# MB_RELAY.net
KiCad netlist of a schematic drawn in Altium Designer
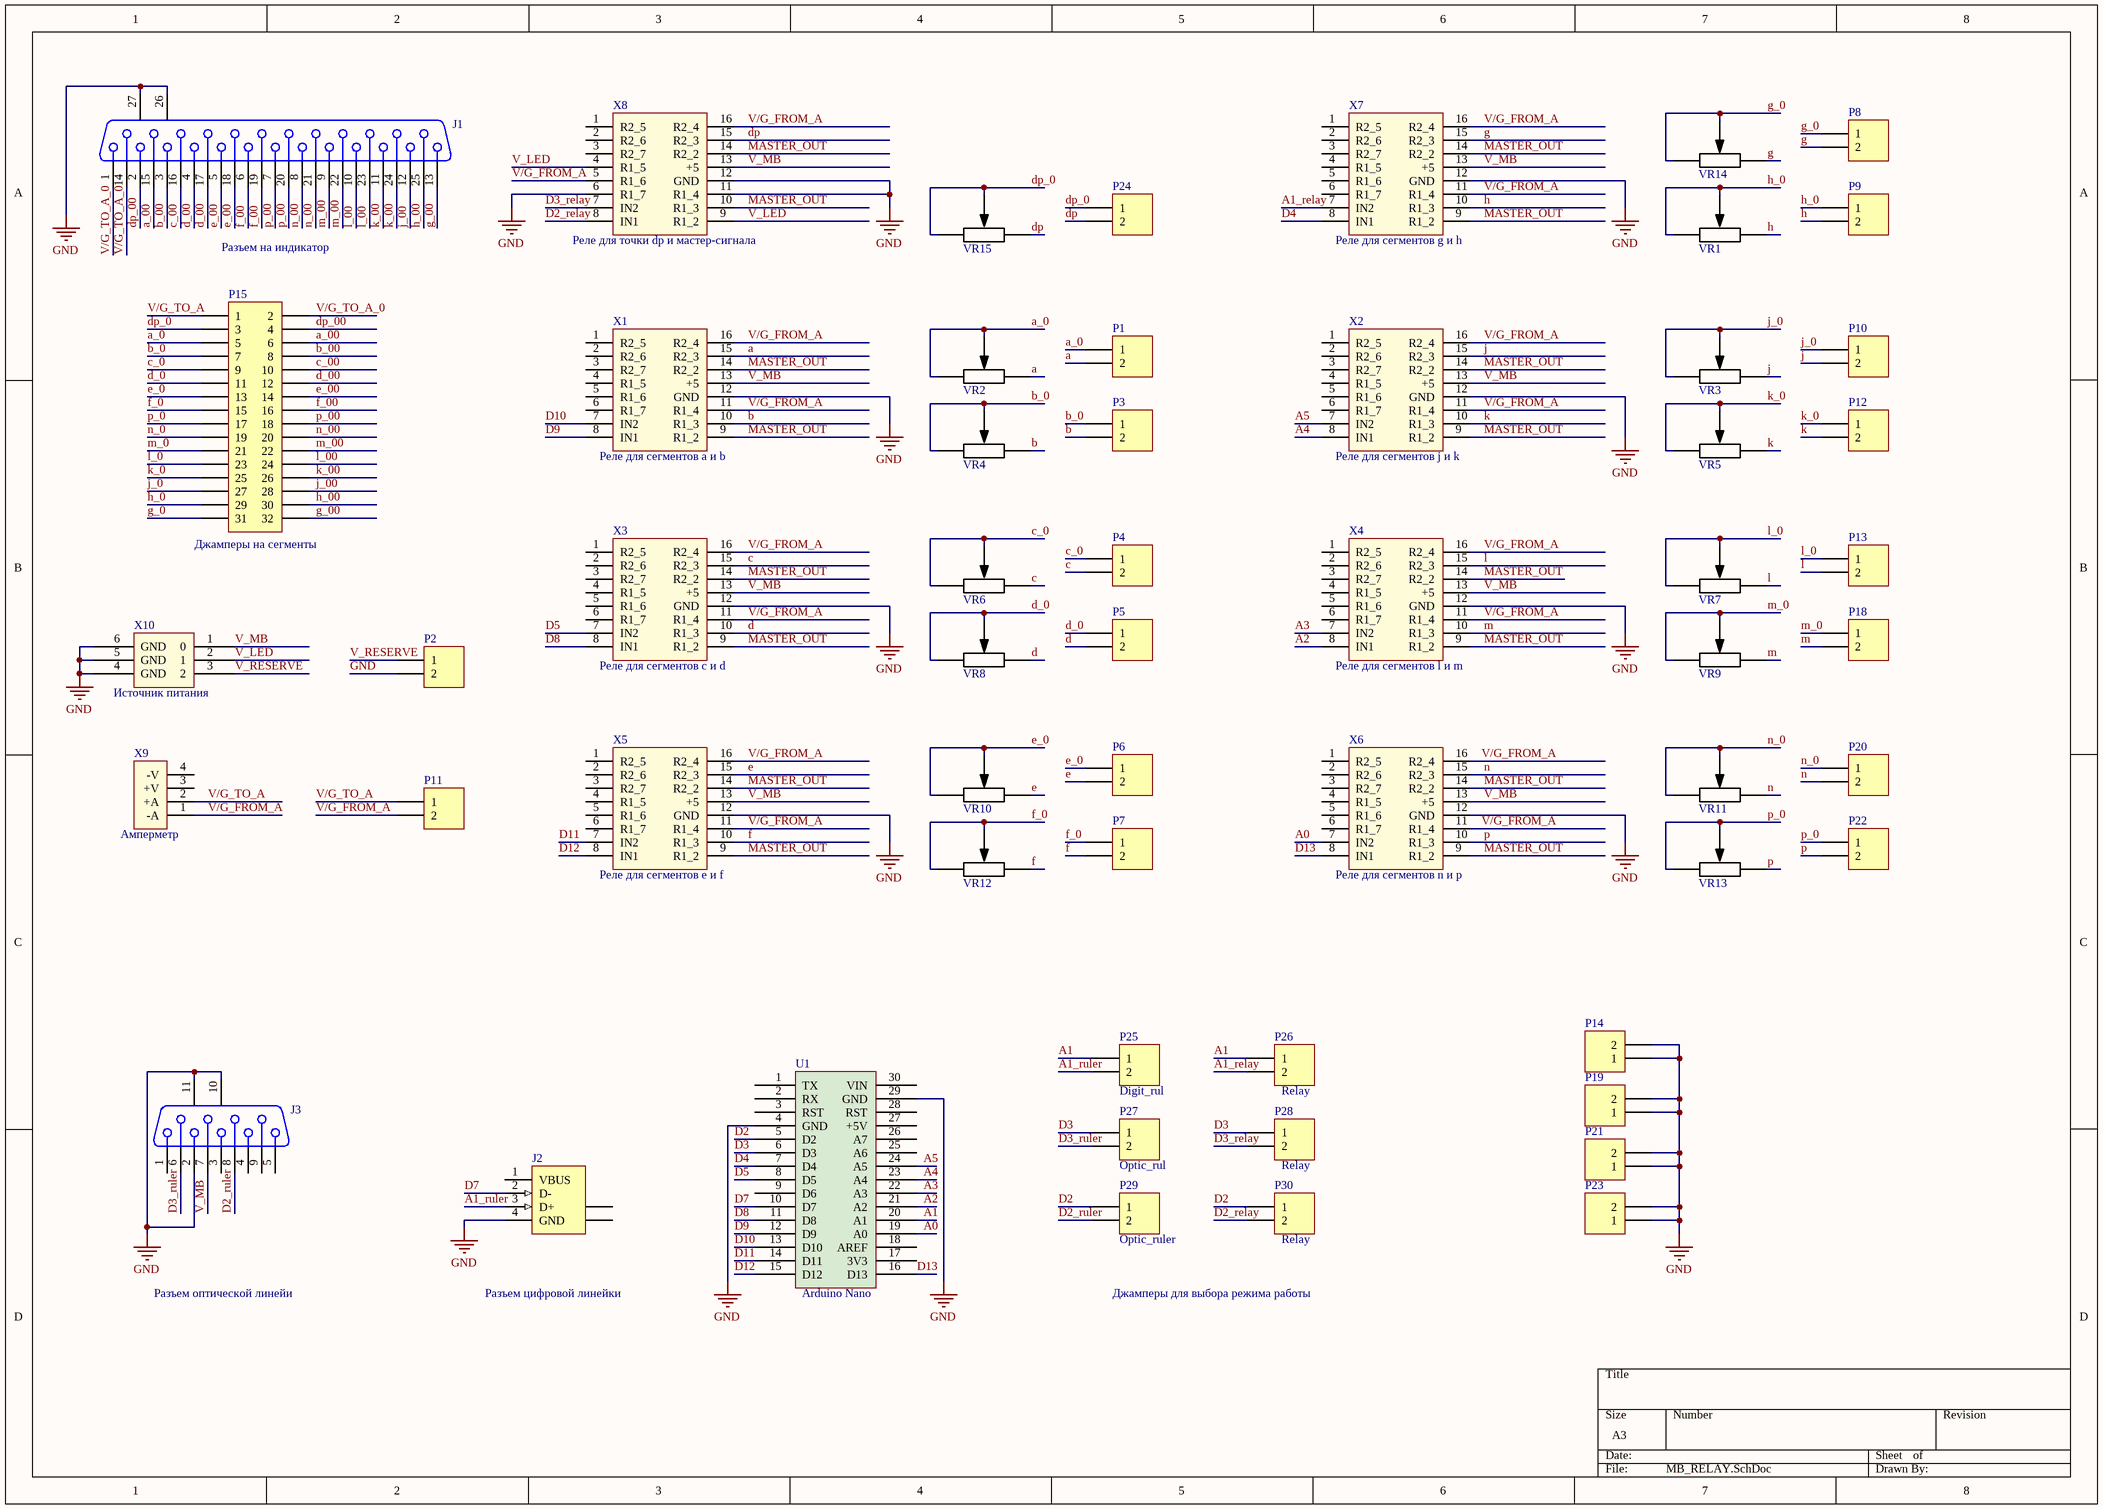
[diagram p0: MB_RELAY.SchDoc]

(export (version "E")
  (design (tool "Eeschema 10.0.6"))
  (components
    (comp (ref "J1")
      (value "D Connector 25")
      (footprint "DSUB1.385-2H25A")
      (description "Receptacle Assembly, 25 Position, Right Angle")
      (fields (field (name "PUBLISHER") "Altium Limited"))
      (libsource (lib "Miscellaneous Connectors") (part "D Connector 25"))
    )
    (comp (ref "J2")
      (value "1-353576-1")
      (footprint "353576")
      (description "USB 1.1, Right Angle, SMT, A Type, Receptacle, 4 Position, White")
      (fields (field (name "PUBLISHER") "Altium Limited"))
      (libsource (lib "AMP Serial Bus USB") (part "1-353576-1"))
    )
    (comp (ref "J3")
      (value "D Connector 9")
      (footprint "DSUB1.385-2H9")
      (description "Receptacle Assembly, 9 Position, Right Angle")
      (fields (field (name "PUBLISHER") "Altium Limited"))
      (libsource (lib "Miscellaneous Connectors") (part "D Connector 9"))
    )
    (comp (ref "P1")
      (value "Header 2")
      (footprint "HDR1X2")
      (description "Header, 2-Pin")
      (fields (field (name "PUBLISHER") "Altium Limited"))
      (libsource (lib "Miscellaneous Connectors") (part "Header 2"))
    )
    (comp (ref "P2")
      (value "Header 2")
      (footprint "HDR1X2")
      (description "Header, 2-Pin")
      (fields (field (name "PUBLISHER") "Altium Limited"))
      (libsource (lib "Miscellaneous Connectors") (part "Header 2"))
    )
    (comp (ref "P3")
      (value "Header 2")
      (footprint "HDR1X2")
      (description "Header, 2-Pin")
      (fields (field (name "PUBLISHER") "Altium Limited"))
      (libsource (lib "Miscellaneous Connectors") (part "Header 2"))
    )
    (comp (ref "P4")
      (value "Header 2")
      (footprint "HDR1X2")
      (description "Header, 2-Pin")
      (fields (field (name "PUBLISHER") "Altium Limited"))
      (libsource (lib "Miscellaneous Connectors") (part "Header 2"))
    )
    (comp (ref "P5")
      (value "Header 2")
      (footprint "HDR1X2")
      (description "Header, 2-Pin")
      (fields (field (name "PUBLISHER") "Altium Limited"))
      (libsource (lib "Miscellaneous Connectors") (part "Header 2"))
    )
    (comp (ref "P6")
      (value "GND")
      (footprint "HDR1X2")
      (description "Header, 2-Pin")
      (fields (field (name "PUBLISHER") "Altium Limited"))
      (libsource (lib "Miscellaneous Connectors") (part "Header 2"))
    )
    (comp (ref "P7")
      (value "GND")
      (footprint "HDR1X2")
      (description "Header, 2-Pin")
      (fields (field (name "PUBLISHER") "Altium Limited"))
      (libsource (lib "Miscellaneous Connectors") (part "Header 2"))
    )
    (comp (ref "P8")
      (value "GND")
      (footprint "HDR1X2")
      (description "Header, 2-Pin")
      (fields (field (name "PUBLISHER") "Altium Limited"))
      (libsource (lib "Miscellaneous Connectors") (part "Header 2"))
    )
    (comp (ref "P9")
      (value "GND")
      (footprint "HDR1X2")
      (description "Header, 2-Pin")
      (fields (field (name "PUBLISHER") "Altium Limited"))
      (libsource (lib "Miscellaneous Connectors") (part "Header 2"))
    )
    (comp (ref "P10")
      (value "Header 2")
      (footprint "HDR1X2")
      (description "Header, 2-Pin")
      (fields (field (name "PUBLISHER") "Altium Limited"))
      (libsource (lib "Miscellaneous Connectors") (part "Header 2"))
    )
    (comp (ref "P11")
      (value "Header 2")
      (footprint "HDR1X2")
      (description "Header, 2-Pin")
      (fields (field (name "PUBLISHER") "Altium Limited"))
      (libsource (lib "Miscellaneous Connectors") (part "Header 2"))
    )
    (comp (ref "P12")
      (value "Header 2")
      (footprint "HDR1X2")
      (description "Header, 2-Pin")
      (fields (field (name "PUBLISHER") "Altium Limited"))
      (libsource (lib "Miscellaneous Connectors") (part "Header 2"))
    )
    (comp (ref "P13")
      (value "GND")
      (footprint "HDR1X2")
      (description "Header, 2-Pin")
      (fields (field (name "PUBLISHER") "Altium Limited"))
      (libsource (lib "Miscellaneous Connectors") (part "Header 2"))
    )
    (comp (ref "P14")
      (value "GND")
      (footprint "HDR1X2")
      (description "Header, 2-Pin")
      (fields (field (name "PUBLISHER") "Altium Limited"))
      (libsource (lib "") (part "Header 2_1"))
    )
    (comp (ref "P15")
      (value "Header 16X2")
      (footprint "HDR2X16")
      (description "Header, 16-Pin, Dual row")
      (fields (field (name "PUBLISHER") "Altium Limited"))
      (libsource (lib "Miscellaneous Connectors") (part "Header 16X2"))
    )
    (comp (ref "P18")
      (value "GND")
      (footprint "HDR1X2")
      (description "Header, 2-Pin")
      (fields (field (name "PUBLISHER") "Altium Limited"))
      (libsource (lib "Miscellaneous Connectors") (part "Header 2"))
    )
    (comp (ref "P19")
      (value "GND")
      (footprint "HDR1X2")
      (description "Header, 2-Pin")
      (fields (field (name "PUBLISHER") "Altium Limited"))
      (libsource (lib "") (part "Header 2_1"))
    )
    (comp (ref "P20")
      (value "GND")
      (footprint "HDR1X2")
      (description "Header, 2-Pin")
      (fields (field (name "PUBLISHER") "Altium Limited"))
      (libsource (lib "Miscellaneous Connectors") (part "Header 2"))
    )
    (comp (ref "P21")
      (value "GND")
      (footprint "HDR1X2")
      (description "Header, 2-Pin")
      (fields (field (name "PUBLISHER") "Altium Limited"))
      (libsource (lib "") (part "Header 2_1"))
    )
    (comp (ref "P22")
      (value "GND")
      (footprint "HDR1X2")
      (description "Header, 2-Pin")
      (fields (field (name "PUBLISHER") "Altium Limited"))
      (libsource (lib "Miscellaneous Connectors") (part "Header 2"))
    )
    (comp (ref "P23")
      (value "GND")
      (footprint "HDR1X2")
      (description "Header, 2-Pin")
      (fields (field (name "PUBLISHER") "Altium Limited"))
      (libsource (lib "") (part "Header 2_1"))
    )
    (comp (ref "P24")
      (value "GND")
      (footprint "HDR1X2")
      (description "Header, 2-Pin")
      (fields (field (name "PUBLISHER") "Altium Limited"))
      (libsource (lib "Miscellaneous Connectors") (part "Header 2"))
    )
    (comp (ref "P25")
      (value "Digit_rul")
      (footprint "HDR1X2")
      (description "Header, 2-Pin")
      (fields (field (name "PUBLISHER") "Altium Limited"))
      (libsource (lib "Miscellaneous Connectors") (part "Header 2"))
    )
    (comp (ref "P26")
      (value "Relay")
      (footprint "HDR1X2")
      (description "Header, 2-Pin")
      (fields (field (name "PUBLISHER") "Altium Limited"))
      (libsource (lib "Miscellaneous Connectors") (part "Header 2"))
    )
    (comp (ref "P27")
      (value "Optic_rul")
      (footprint "HDR1X2")
      (description "Header, 2-Pin")
      (fields (field (name "PUBLISHER") "Altium Limited"))
      (libsource (lib "Miscellaneous Connectors") (part "Header 2"))
    )
    (comp (ref "P28")
      (value "Relay")
      (footprint "HDR1X2")
      (description "Header, 2-Pin")
      (fields (field (name "PUBLISHER") "Altium Limited"))
      (libsource (lib "Miscellaneous Connectors") (part "Header 2"))
    )
    (comp (ref "P29")
      (value "Optic_ruler")
      (footprint "HDR1X2")
      (description "Header, 2-Pin")
      (fields (field (name "PUBLISHER") "Altium Limited"))
      (libsource (lib "Miscellaneous Connectors") (part "Header 2"))
    )
    (comp (ref "P30")
      (value "Relay")
      (footprint "HDR1X2")
      (description "Header, 2-Pin")
      (fields (field (name "PUBLISHER") "Altium Limited"))
      (libsource (lib "Miscellaneous Connectors") (part "Header 2"))
    )
    (comp (ref "U1")
      (value "Arduino Nano")
      (footprint "PCBComponent_1")
      (libsource (lib "Nano") (part "Component_1"))
    )
    (comp (ref "VR1")
      (value "RES 3266W")
      (footprint "aab_Passive:RES 3266W")
      (libsource (lib "aab_Schlib") (part "RES 3266W"))
    )
    (comp (ref "VR2")
      (value "Переменнный резистор для")
      (footprint "aab_Passive:RES 3266W")
      (libsource (lib "aab_Schlib") (part "RES 3266W"))
    )
    (comp (ref "VR3")
      (value "RES 3266W")
      (footprint "aab_Passive:RES 3266W")
      (libsource (lib "aab_Schlib") (part "RES 3266W"))
    )
    (comp (ref "VR4")
      (value "RES 3266W")
      (footprint "aab_Passive:RES 3266W")
      (libsource (lib "aab_Schlib") (part "RES 3266W"))
    )
    (comp (ref "VR5")
      (value "RES 3266W")
      (footprint "aab_Passive:RES 3266W")
      (libsource (lib "aab_Schlib") (part "RES 3266W"))
    )
    (comp (ref "VR6")
      (value "RES 3266W")
      (footprint "aab_Passive:RES 3266W")
      (libsource (lib "aab_Schlib") (part "RES 3266W"))
    )
    (comp (ref "VR7")
      (value "RES 3266W")
      (footprint "aab_Passive:RES 3266W")
      (libsource (lib "aab_Schlib") (part "RES 3266W"))
    )
    (comp (ref "VR8")
      (value "RES 3266W")
      (footprint "aab_Passive:RES 3266W")
      (libsource (lib "aab_Schlib") (part "RES 3266W"))
    )
    (comp (ref "VR9")
      (value "RES 3266W")
      (footprint "aab_Passive:RES 3266W")
      (libsource (lib "aab_Schlib") (part "RES 3266W"))
    )
    (comp (ref "VR10")
      (value "RES 3266W")
      (footprint "aab_Passive:RES 3266W")
      (libsource (lib "aab_Schlib") (part "RES 3266W"))
    )
    (comp (ref "VR11")
      (value "RES 3266W")
      (footprint "aab_Passive:RES 3266W")
      (libsource (lib "aab_Schlib") (part "RES 3266W"))
    )
    (comp (ref "VR12")
      (value "RES 3266W")
      (footprint "aab_Passive:RES 3266W")
      (libsource (lib "aab_Schlib") (part "RES 3266W"))
    )
    (comp (ref "VR13")
      (value "RES 3266W")
      (footprint "aab_Passive:RES 3266W")
      (libsource (lib "aab_Schlib") (part "RES 3266W"))
    )
    (comp (ref "VR14")
      (value "RES 3266W")
      (footprint "aab_Passive:RES 3266W")
      (libsource (lib "aab_Schlib") (part "RES 3266W"))
    )
    (comp (ref "VR15")
      (value "RES 3266W")
      (footprint "aab_Passive:RES 3266W")
      (libsource (lib "aab_Schlib") (part "RES 3266W"))
    )
    (comp (ref "X1")
      (value "Реле для сегментов a и b")
      (footprint "MEZ_RELAY")
      (libsource (lib "msp_SchLib") (part "MEZ_RELAY"))
    )
    (comp (ref "X2")
      (value "Реле для сегментов j и k")
      (footprint "MEZ_RELAY")
      (libsource (lib "msp_SchLib") (part "MEZ_RELAY"))
    )
    (comp (ref "X3")
      (value "Реле для сегментов c и d")
      (footprint "MEZ_RELAY")
      (libsource (lib "msp_SchLib") (part "MEZ_RELAY"))
    )
    (comp (ref "X4")
      (value "Реле для сегментов l и m")
      (footprint "MEZ_RELAY")
      (libsource (lib "msp_SchLib") (part "MEZ_RELAY"))
    )
    (comp (ref "X5")
      (value "Реле для сегментов e и f")
      (footprint "MEZ_RELAY")
      (libsource (lib "msp_SchLib") (part "MEZ_RELAY"))
    )
    (comp (ref "X6")
      (value "Реле для сегментов n и p")
      (footprint "MEZ_RELAY")
      (libsource (lib "msp_SchLib") (part "MEZ_RELAY"))
    )
    (comp (ref "X7")
      (value "Реле для сегментов g и h")
      (footprint "MEZ_RELAY")
      (libsource (lib "msp_SchLib") (part "MEZ_RELAY"))
    )
    (comp (ref "X8")
      (value "Реле для точки dp и мастер-сигнала")
      (footprint "MEZ_RELAY")
      (libsource (lib "msp_SchLib") (part "MEZ_RELAY"))
    )
    (comp (ref "X9")
      (value "Амперметр")
      (footprint "vpl_Passive:AMP_VOLTMETER")
      (libsource (lib "msp_SchLib") (part "AMP_VOLTMETR"))
    )
    (comp (ref "X10")
      (value "Источник питания")
      (footprint "vpl_Passive:POWER")
      (libsource (lib "msp_SchLib") (part "POWER"))
    )
  )
  (nets
    (net (code "1") (name "/A0") (class "Default")
      (node (ref "U1") (pin "19") (pinfunction "A0_19") (pintype "passive"))
      (node (ref "X6") (pin "7") (pinfunction "IN2_7") (pintype "passive"))
    )
    (net (code "2") (name "/A1") (class "Default")
      (node (ref "P25") (pin "1") (pinfunction "1_1") (pintype "passive"))
      (node (ref "P26") (pin "1") (pinfunction "1_1") (pintype "passive"))
      (node (ref "U1") (pin "20") (pinfunction "A1_20") (pintype "passive"))
    )
    (net (code "3") (name "/A1_relay") (class "Default")
      (node (ref "P26") (pin "2") (pinfunction "2_2") (pintype "passive"))
      (node (ref "X7") (pin "7") (pinfunction "IN2_7") (pintype "passive"))
    )
    (net (code "4") (name "/A1_ruler") (class "Default")
      (node (ref "J2") (pin "3") (pinfunction "D+_3") (pintype "input"))
      (node (ref "P25") (pin "2") (pinfunction "2_2") (pintype "passive"))
    )
    (net (code "5") (name "/A2") (class "Default")
      (node (ref "U1") (pin "21") (pinfunction "A2_21") (pintype "passive"))
      (node (ref "X4") (pin "8") (pinfunction "IN1_8") (pintype "passive"))
    )
    (net (code "6") (name "/A3") (class "Default")
      (node (ref "U1") (pin "22") (pinfunction "A3_22") (pintype "passive"))
      (node (ref "X4") (pin "7") (pinfunction "IN2_7") (pintype "passive"))
    )
    (net (code "7") (name "/A4") (class "Default")
      (node (ref "U1") (pin "23") (pinfunction "A4_23") (pintype "passive"))
      (node (ref "X2") (pin "8") (pinfunction "IN1_8") (pintype "passive"))
    )
    (net (code "8") (name "/A5") (class "Default")
      (node (ref "U1") (pin "24") (pinfunction "A5_24") (pintype "passive"))
      (node (ref "X2") (pin "7") (pinfunction "IN2_7") (pintype "passive"))
    )
    (net (code "9") (name "/D2") (class "Default")
      (node (ref "P29") (pin "1") (pinfunction "1_1") (pintype "passive"))
      (node (ref "P30") (pin "1") (pinfunction "1_1") (pintype "passive"))
      (node (ref "U1") (pin "5") (pinfunction "D2_5") (pintype "passive"))
    )
    (net (code "10") (name "/D2_relay") (class "Default")
      (node (ref "P30") (pin "2") (pinfunction "2_2") (pintype "passive"))
      (node (ref "X8") (pin "8") (pinfunction "IN1_8") (pintype "passive"))
    )
    (net (code "11") (name "/D2_ruler") (class "Default")
      (node (ref "J3") (pin "8") (pinfunction "8_8") (pintype "passive"))
      (node (ref "P29") (pin "2") (pinfunction "2_2") (pintype "passive"))
    )
    (net (code "12") (name "/D3") (class "Default")
      (node (ref "P27") (pin "1") (pinfunction "1_1") (pintype "passive"))
      (node (ref "P28") (pin "1") (pinfunction "1_1") (pintype "passive"))
      (node (ref "U1") (pin "6") (pinfunction "D3_6") (pintype "passive"))
    )
    (net (code "13") (name "/D3_relay") (class "Default")
      (node (ref "P28") (pin "2") (pinfunction "2_2") (pintype "passive"))
      (node (ref "X8") (pin "7") (pinfunction "IN2_7") (pintype "passive"))
    )
    (net (code "14") (name "/D3_ruler") (class "Default")
      (node (ref "J3") (pin "6") (pinfunction "6_6") (pintype "passive"))
      (node (ref "P27") (pin "2") (pinfunction "2_2") (pintype "passive"))
    )
    (net (code "15") (name "/D4") (class "Default")
      (node (ref "U1") (pin "7") (pinfunction "D4_7") (pintype "passive"))
      (node (ref "X7") (pin "8") (pinfunction "IN1_8") (pintype "passive"))
    )
    (net (code "16") (name "/D5") (class "Default")
      (node (ref "U1") (pin "8") (pinfunction "D5_8") (pintype "passive"))
      (node (ref "X3") (pin "7") (pinfunction "IN2_7") (pintype "passive"))
    )
    (net (code "17") (name "/D7") (class "Default")
      (node (ref "J2") (pin "2") (pinfunction "D-_2") (pintype "input"))
      (node (ref "U1") (pin "10") (pinfunction "D7_10") (pintype "passive"))
    )
    (net (code "18") (name "/D8") (class "Default")
      (node (ref "U1") (pin "11") (pinfunction "D8_11") (pintype "passive"))
      (node (ref "X3") (pin "8") (pinfunction "IN1_8") (pintype "passive"))
    )
    (net (code "19") (name "/D9") (class "Default")
      (node (ref "U1") (pin "12") (pinfunction "D9_12") (pintype "passive"))
      (node (ref "X1") (pin "8") (pinfunction "IN1_8") (pintype "passive"))
    )
    (net (code "20") (name "/D10") (class "Default")
      (node (ref "U1") (pin "13") (pinfunction "D10_13") (pintype "passive"))
      (node (ref "X1") (pin "7") (pinfunction "IN2_7") (pintype "passive"))
    )
    (net (code "21") (name "/D11") (class "Default")
      (node (ref "U1") (pin "14") (pinfunction "D11_14") (pintype "passive"))
      (node (ref "X5") (pin "7") (pinfunction "IN2_7") (pintype "passive"))
    )
    (net (code "22") (name "/D12") (class "Default")
      (node (ref "U1") (pin "15") (pinfunction "D12_15") (pintype "passive"))
      (node (ref "X5") (pin "8") (pinfunction "IN1_8") (pintype "passive"))
    )
    (net (code "23") (name "/D13") (class "Default")
      (node (ref "U1") (pin "16") (pinfunction "D13_16") (pintype "passive"))
      (node (ref "X6") (pin "8") (pinfunction "IN1_8") (pintype "passive"))
    )
    (net (code "24") (name "/MASTER_OUT") (class "Default")
      (node (ref "X1") (pin "14") (pinfunction "R2_2_14") (pintype "passive"))
      (node (ref "X1") (pin "9") (pinfunction "R1_2_9") (pintype "passive"))
      (node (ref "X2") (pin "14") (pinfunction "R2_2_14") (pintype "passive"))
      (node (ref "X2") (pin "9") (pinfunction "R1_2_9") (pintype "passive"))
      (node (ref "X3") (pin "14") (pinfunction "R2_2_14") (pintype "passive"))
      (node (ref "X3") (pin "9") (pinfunction "R1_2_9") (pintype "passive"))
      (node (ref "X4") (pin "14") (pinfunction "R2_2_14") (pintype "passive"))
      (node (ref "X4") (pin "9") (pinfunction "R1_2_9") (pintype "passive"))
      (node (ref "X5") (pin "14") (pinfunction "R2_2_14") (pintype "passive"))
      (node (ref "X5") (pin "9") (pinfunction "R1_2_9") (pintype "passive"))
      (node (ref "X6") (pin "14") (pinfunction "R2_2_14") (pintype "passive"))
      (node (ref "X6") (pin "9") (pinfunction "R1_2_9") (pintype "passive"))
      (node (ref "X7") (pin "14") (pinfunction "R2_2_14") (pintype "passive"))
      (node (ref "X7") (pin "9") (pinfunction "R1_2_9") (pintype "passive"))
      (node (ref "X8") (pin "10") (pinfunction "R1_3_10") (pintype "passive"))
      (node (ref "X8") (pin "14") (pinfunction "R2_2_14") (pintype "passive"))
    )
    (net (code "25") (name "/V_LED") (class "Default")
      (node (ref "X10") (pin "2") (pinfunction "1_2") (pintype "passive"))
      (node (ref "X8") (pin "4") (pinfunction "R1_5_4") (pintype "passive"))
      (node (ref "X8") (pin "9") (pinfunction "R1_2_9") (pintype "passive"))
    )
    (net (code "26") (name "/V_MB") (class "Default")
      (node (ref "J3") (pin "7") (pinfunction "7_7") (pintype "passive"))
      (node (ref "X1") (pin "13") (pinfunction "+5_13") (pintype "passive"))
      (node (ref "X10") (pin "1") (pinfunction "0_1") (pintype "passive"))
      (node (ref "X2") (pin "13") (pinfunction "+5_13") (pintype "passive"))
      (node (ref "X3") (pin "13") (pinfunction "+5_13") (pintype "passive"))
      (node (ref "X4") (pin "13") (pinfunction "+5_13") (pintype "passive"))
      (node (ref "X5") (pin "13") (pinfunction "+5_13") (pintype "passive"))
      (node (ref "X6") (pin "13") (pinfunction "+5_13") (pintype "passive"))
      (node (ref "X7") (pin "13") (pinfunction "+5_13") (pintype "passive"))
      (node (ref "X8") (pin "13") (pinfunction "+5_13") (pintype "passive"))
    )
    (net (code "27") (name "/V_RESERVE") (class "Default")
      (node (ref "P2") (pin "1") (pinfunction "1_1") (pintype "passive"))
      (node (ref "X10") (pin "3") (pinfunction "2_3") (pintype "passive"))
    )
    (net (code "28") (name "/V{slash}G_FROM_A") (class "Default")
      (node (ref "P11") (pin "2") (pinfunction "2_2") (pintype "passive"))
      (node (ref "X1") (pin "11") (pinfunction "R1_4_11") (pintype "passive"))
      (node (ref "X1") (pin "16") (pinfunction "R2_4_16") (pintype "passive"))
      (node (ref "X2") (pin "11") (pinfunction "R1_4_11") (pintype "passive"))
      (node (ref "X2") (pin "16") (pinfunction "R2_4_16") (pintype "passive"))
      (node (ref "X3") (pin "11") (pinfunction "R1_4_11") (pintype "passive"))
      (node (ref "X3") (pin "16") (pinfunction "R2_4_16") (pintype "passive"))
      (node (ref "X4") (pin "11") (pinfunction "R1_4_11") (pintype "passive"))
      (node (ref "X4") (pin "16") (pinfunction "R2_4_16") (pintype "passive"))
      (node (ref "X5") (pin "11") (pinfunction "R1_4_11") (pintype "passive"))
      (node (ref "X5") (pin "16") (pinfunction "R2_4_16") (pintype "passive"))
      (node (ref "X6") (pin "11") (pinfunction "R1_4_11") (pintype "passive"))
      (node (ref "X6") (pin "16") (pinfunction "R2_4_16") (pintype "passive"))
      (node (ref "X7") (pin "11") (pinfunction "R1_4_11") (pintype "passive"))
      (node (ref "X7") (pin "16") (pinfunction "R2_4_16") (pintype "passive"))
      (node (ref "X8") (pin "16") (pinfunction "R2_4_16") (pintype "passive"))
      (node (ref "X8") (pin "5") (pinfunction "R1_6_5") (pintype "passive"))
      (node (ref "X9") (pin "1") (pinfunction "-A_1") (pintype "passive"))
    )
    (net (code "29") (name "/V{slash}G_TO_A") (class "Default")
      (node (ref "P11") (pin "1") (pinfunction "1_1") (pintype "passive"))
      (node (ref "P15") (pin "1") (pinfunction "1_1") (pintype "passive"))
      (node (ref "X9") (pin "2") (pinfunction "+A_2") (pintype "passive"))
    )
    (net (code "30") (name "/V{slash}G_TO_A_0") (class "Default")
      (node (ref "J1") (pin "1") (pinfunction "1_1") (pintype "passive"))
      (node (ref "J1") (pin "14") (pinfunction "14_14") (pintype "passive"))
      (node (ref "P15") (pin "2") (pinfunction "2_2") (pintype "passive"))
    )
    (net (code "31") (name "/a") (class "Default")
      (node (ref "P1") (pin "2") (pinfunction "2_2") (pintype "passive"))
      (node (ref "VR2") (pin "3") (pinfunction "3_3") (pintype "passive"))
      (node (ref "X1") (pin "15") (pinfunction "R2_3_15") (pintype "passive"))
    )
    (net (code "32") (name "/a_00") (class "Default")
      (node (ref "J1") (pin "15") (pinfunction "15_15") (pintype "passive"))
      (node (ref "P15") (pin "6") (pinfunction "6_6") (pintype "passive"))
    )
    (net (code "33") (name "/a_0") (class "Default")
      (node (ref "P1") (pin "1") (pinfunction "1_1") (pintype "passive"))
      (node (ref "P15") (pin "5") (pinfunction "5_5") (pintype "passive"))
      (node (ref "VR2") (pin "1") (pinfunction "1_1") (pintype "passive"))
      (node (ref "VR2") (pin "2") (pinfunction "2_2") (pintype "passive"))
    )
    (net (code "34") (name "/b") (class "Default")
      (node (ref "P3") (pin "2") (pinfunction "2_2") (pintype "passive"))
      (node (ref "VR4") (pin "3") (pinfunction "3_3") (pintype "passive"))
      (node (ref "X1") (pin "10") (pinfunction "R1_3_10") (pintype "passive"))
    )
    (net (code "35") (name "/b_0") (class "Default")
      (node (ref "P15") (pin "7") (pinfunction "7_7") (pintype "passive"))
      (node (ref "P3") (pin "1") (pinfunction "1_1") (pintype "passive"))
      (node (ref "VR4") (pin "1") (pinfunction "1_1") (pintype "passive"))
      (node (ref "VR4") (pin "2") (pinfunction "2_2") (pintype "passive"))
    )
    (net (code "36") (name "/b_00") (class "Default")
      (node (ref "J1") (pin "3") (pinfunction "3_3") (pintype "passive"))
      (node (ref "P15") (pin "8") (pinfunction "8_8") (pintype "passive"))
    )
    (net (code "37") (name "/c") (class "Default")
      (node (ref "P4") (pin "2") (pinfunction "2_2") (pintype "passive"))
      (node (ref "VR6") (pin "3") (pinfunction "3_3") (pintype "passive"))
      (node (ref "X3") (pin "15") (pinfunction "R2_3_15") (pintype "passive"))
    )
    (net (code "38") (name "/c_00") (class "Default")
      (node (ref "J1") (pin "16") (pinfunction "16_16") (pintype "passive"))
      (node (ref "P15") (pin "10") (pinfunction "10_10") (pintype "passive"))
    )
    (net (code "39") (name "/c_0") (class "Default")
      (node (ref "P15") (pin "9") (pinfunction "9_9") (pintype "passive"))
      (node (ref "P4") (pin "1") (pinfunction "1_1") (pintype "passive"))
      (node (ref "VR6") (pin "1") (pinfunction "1_1") (pintype "passive"))
      (node (ref "VR6") (pin "2") (pinfunction "2_2") (pintype "passive"))
    )
    (net (code "40") (name "/d") (class "Default")
      (node (ref "P5") (pin "2") (pinfunction "2_2") (pintype "passive"))
      (node (ref "VR8") (pin "3") (pinfunction "3_3") (pintype "passive"))
      (node (ref "X3") (pin "10") (pinfunction "R1_3_10") (pintype "passive"))
    )
    (net (code "41") (name "/d_0") (class "Default")
      (node (ref "P15") (pin "11") (pinfunction "11_11") (pintype "passive"))
      (node (ref "P5") (pin "1") (pinfunction "1_1") (pintype "passive"))
      (node (ref "VR8") (pin "1") (pinfunction "1_1") (pintype "passive"))
      (node (ref "VR8") (pin "2") (pinfunction "2_2") (pintype "passive"))
    )
    (net (code "42") (name "/d_00") (class "Default")
      (node (ref "J1") (pin "17") (pinfunction "17_17") (pintype "passive"))
      (node (ref "J1") (pin "4") (pinfunction "4_4") (pintype "passive"))
      (node (ref "P15") (pin "12") (pinfunction "12_12") (pintype "passive"))
    )
    (net (code "43") (name "/dp") (class "Default")
      (node (ref "P24") (pin "2") (pinfunction "2_2") (pintype "passive"))
      (node (ref "VR15") (pin "3") (pinfunction "3_3") (pintype "passive"))
      (node (ref "X8") (pin "15") (pinfunction "R2_3_15") (pintype "passive"))
    )
    (net (code "44") (name "/dp_00") (class "Default")
      (node (ref "J1") (pin "2") (pinfunction "2_2") (pintype "passive"))
      (node (ref "P15") (pin "4") (pinfunction "4_4") (pintype "passive"))
    )
    (net (code "45") (name "/dp_0") (class "Default")
      (node (ref "P15") (pin "3") (pinfunction "3_3") (pintype "passive"))
      (node (ref "P24") (pin "1") (pinfunction "1_1") (pintype "passive"))
      (node (ref "VR15") (pin "1") (pinfunction "1_1") (pintype "passive"))
      (node (ref "VR15") (pin "2") (pinfunction "2_2") (pintype "passive"))
    )
    (net (code "46") (name "/e") (class "Default")
      (node (ref "P6") (pin "2") (pinfunction "2_2") (pintype "passive"))
      (node (ref "VR10") (pin "3") (pinfunction "3_3") (pintype "passive"))
      (node (ref "X5") (pin "15") (pinfunction "R2_3_15") (pintype "passive"))
    )
    (net (code "47") (name "/e_0") (class "Default")
      (node (ref "P15") (pin "13") (pinfunction "13_13") (pintype "passive"))
      (node (ref "P6") (pin "1") (pinfunction "1_1") (pintype "passive"))
      (node (ref "VR10") (pin "1") (pinfunction "1_1") (pintype "passive"))
      (node (ref "VR10") (pin "2") (pinfunction "2_2") (pintype "passive"))
    )
    (net (code "48") (name "/e_00") (class "Default")
      (node (ref "J1") (pin "18") (pinfunction "18_18") (pintype "passive"))
      (node (ref "J1") (pin "5") (pinfunction "5_5") (pintype "passive"))
      (node (ref "P15") (pin "14") (pinfunction "14_14") (pintype "passive"))
    )
    (net (code "49") (name "/f") (class "Default")
      (node (ref "P7") (pin "2") (pinfunction "2_2") (pintype "passive"))
      (node (ref "VR12") (pin "3") (pinfunction "3_3") (pintype "passive"))
      (node (ref "X5") (pin "10") (pinfunction "R1_3_10") (pintype "passive"))
    )
    (net (code "50") (name "/f_0") (class "Default")
      (node (ref "P15") (pin "15") (pinfunction "15_15") (pintype "passive"))
      (node (ref "P7") (pin "1") (pinfunction "1_1") (pintype "passive"))
      (node (ref "VR12") (pin "1") (pinfunction "1_1") (pintype "passive"))
      (node (ref "VR12") (pin "2") (pinfunction "2_2") (pintype "passive"))
    )
    (net (code "51") (name "/f_00") (class "Default")
      (node (ref "J1") (pin "19") (pinfunction "19_19") (pintype "passive"))
      (node (ref "J1") (pin "6") (pinfunction "6_6") (pintype "passive"))
      (node (ref "P15") (pin "16") (pinfunction "16_16") (pintype "passive"))
    )
    (net (code "52") (name "/g") (class "Default")
      (node (ref "P8") (pin "2") (pinfunction "2_2") (pintype "passive"))
      (node (ref "VR14") (pin "3") (pinfunction "3_3") (pintype "passive"))
      (node (ref "X7") (pin "15") (pinfunction "R2_3_15") (pintype "passive"))
    )
    (net (code "53") (name "/g_00") (class "Default")
      (node (ref "J1") (pin "13") (pinfunction "13_13") (pintype "passive"))
      (node (ref "P15") (pin "32") (pinfunction "32_32") (pintype "passive"))
    )
    (net (code "54") (name "/g_0") (class "Default")
      (node (ref "P15") (pin "31") (pinfunction "31_31") (pintype "passive"))
      (node (ref "P8") (pin "1") (pinfunction "1_1") (pintype "passive"))
      (node (ref "VR14") (pin "1") (pinfunction "1_1") (pintype "passive"))
      (node (ref "VR14") (pin "2") (pinfunction "2_2") (pintype "passive"))
    )
    (net (code "55") (name "/h") (class "Default")
      (node (ref "P9") (pin "2") (pinfunction "2_2") (pintype "passive"))
      (node (ref "VR1") (pin "3") (pinfunction "3_3") (pintype "passive"))
      (node (ref "X7") (pin "10") (pinfunction "R1_3_10") (pintype "passive"))
    )
    (net (code "56") (name "/h_0") (class "Default")
      (node (ref "P15") (pin "29") (pinfunction "29_29") (pintype "passive"))
      (node (ref "P9") (pin "1") (pinfunction "1_1") (pintype "passive"))
      (node (ref "VR1") (pin "1") (pinfunction "1_1") (pintype "passive"))
      (node (ref "VR1") (pin "2") (pinfunction "2_2") (pintype "passive"))
    )
    (net (code "57") (name "/h_00") (class "Default")
      (node (ref "J1") (pin "25") (pinfunction "25_25") (pintype "passive"))
      (node (ref "P15") (pin "30") (pinfunction "30_30") (pintype "passive"))
    )
    (net (code "58") (name "/j") (class "Default")
      (node (ref "P10") (pin "2") (pinfunction "2_2") (pintype "passive"))
      (node (ref "VR3") (pin "3") (pinfunction "3_3") (pintype "passive"))
      (node (ref "X2") (pin "15") (pinfunction "R2_3_15") (pintype "passive"))
    )
    (net (code "59") (name "/j_0") (class "Default")
      (node (ref "P10") (pin "1") (pinfunction "1_1") (pintype "passive"))
      (node (ref "P15") (pin "27") (pinfunction "27_27") (pintype "passive"))
      (node (ref "VR3") (pin "1") (pinfunction "1_1") (pintype "passive"))
      (node (ref "VR3") (pin "2") (pinfunction "2_2") (pintype "passive"))
    )
    (net (code "60") (name "/j_00") (class "Default")
      (node (ref "J1") (pin "12") (pinfunction "12_12") (pintype "passive"))
      (node (ref "P15") (pin "28") (pinfunction "28_28") (pintype "passive"))
    )
    (net (code "61") (name "/k") (class "Default")
      (node (ref "P12") (pin "2") (pinfunction "2_2") (pintype "passive"))
      (node (ref "VR5") (pin "3") (pinfunction "3_3") (pintype "passive"))
      (node (ref "X2") (pin "10") (pinfunction "R1_3_10") (pintype "passive"))
    )
    (net (code "62") (name "/k_0") (class "Default")
      (node (ref "P12") (pin "1") (pinfunction "1_1") (pintype "passive"))
      (node (ref "P15") (pin "25") (pinfunction "25_25") (pintype "passive"))
      (node (ref "VR5") (pin "1") (pinfunction "1_1") (pintype "passive"))
      (node (ref "VR5") (pin "2") (pinfunction "2_2") (pintype "passive"))
    )
    (net (code "63") (name "/k_00") (class "Default")
      (node (ref "J1") (pin "11") (pinfunction "11_11") (pintype "passive"))
      (node (ref "J1") (pin "24") (pinfunction "24_24") (pintype "passive"))
      (node (ref "P15") (pin "26") (pinfunction "26_26") (pintype "passive"))
    )
    (net (code "64") (name "/l") (class "Default")
      (node (ref "P13") (pin "2") (pinfunction "2_2") (pintype "passive"))
      (node (ref "VR7") (pin "3") (pinfunction "3_3") (pintype "passive"))
      (node (ref "X4") (pin "15") (pinfunction "R2_3_15") (pintype "passive"))
    )
    (net (code "65") (name "/l_0") (class "Default")
      (node (ref "P13") (pin "1") (pinfunction "1_1") (pintype "passive"))
      (node (ref "P15") (pin "23") (pinfunction "23_23") (pintype "passive"))
      (node (ref "VR7") (pin "1") (pinfunction "1_1") (pintype "passive"))
      (node (ref "VR7") (pin "2") (pinfunction "2_2") (pintype "passive"))
    )
    (net (code "66") (name "/l_00") (class "Default")
      (node (ref "J1") (pin "10") (pinfunction "10_10") (pintype "passive"))
      (node (ref "J1") (pin "23") (pinfunction "23_23") (pintype "passive"))
      (node (ref "P15") (pin "24") (pinfunction "24_24") (pintype "passive"))
    )
    (net (code "67") (name "/m") (class "Default")
      (node (ref "P18") (pin "2") (pinfunction "2_2") (pintype "passive"))
      (node (ref "VR9") (pin "3") (pinfunction "3_3") (pintype "passive"))
      (node (ref "X4") (pin "10") (pinfunction "R1_3_10") (pintype "passive"))
    )
    (net (code "68") (name "/m_00") (class "Default")
      (node (ref "J1") (pin "22") (pinfunction "22_22") (pintype "passive"))
      (node (ref "J1") (pin "9") (pinfunction "9_9") (pintype "passive"))
      (node (ref "P15") (pin "22") (pinfunction "22_22") (pintype "passive"))
    )
    (net (code "69") (name "/m_0") (class "Default")
      (node (ref "P15") (pin "21") (pinfunction "21_21") (pintype "passive"))
      (node (ref "P18") (pin "1") (pinfunction "1_1") (pintype "passive"))
      (node (ref "VR9") (pin "1") (pinfunction "1_1") (pintype "passive"))
      (node (ref "VR9") (pin "2") (pinfunction "2_2") (pintype "passive"))
    )
    (net (code "70") (name "/n") (class "Default")
      (node (ref "P20") (pin "2") (pinfunction "2_2") (pintype "passive"))
      (node (ref "VR11") (pin "3") (pinfunction "3_3") (pintype "passive"))
      (node (ref "X6") (pin "15") (pinfunction "R2_3_15") (pintype "passive"))
    )
    (net (code "71") (name "/n_0") (class "Default")
      (node (ref "P15") (pin "19") (pinfunction "19_19") (pintype "passive"))
      (node (ref "P20") (pin "1") (pinfunction "1_1") (pintype "passive"))
      (node (ref "VR11") (pin "1") (pinfunction "1_1") (pintype "passive"))
      (node (ref "VR11") (pin "2") (pinfunction "2_2") (pintype "passive"))
    )
    (net (code "72") (name "/n_00") (class "Default")
      (node (ref "J1") (pin "21") (pinfunction "21_21") (pintype "passive"))
      (node (ref "J1") (pin "8") (pinfunction "8_8") (pintype "passive"))
      (node (ref "P15") (pin "20") (pinfunction "20_20") (pintype "passive"))
    )
    (net (code "73") (name "/p") (class "Default")
      (node (ref "P22") (pin "2") (pinfunction "2_2") (pintype "passive"))
      (node (ref "VR13") (pin "3") (pinfunction "3_3") (pintype "passive"))
      (node (ref "X6") (pin "10") (pinfunction "R1_3_10") (pintype "passive"))
    )
    (net (code "74") (name "/p_0") (class "Default")
      (node (ref "P15") (pin "17") (pinfunction "17_17") (pintype "passive"))
      (node (ref "P22") (pin "1") (pinfunction "1_1") (pintype "passive"))
      (node (ref "VR13") (pin "1") (pinfunction "1_1") (pintype "passive"))
      (node (ref "VR13") (pin "2") (pinfunction "2_2") (pintype "passive"))
    )
    (net (code "75") (name "/p_00") (class "Default")
      (node (ref "J1") (pin "20") (pinfunction "20_20") (pintype "passive"))
      (node (ref "J1") (pin "7") (pinfunction "7_7") (pintype "passive"))
      (node (ref "P15") (pin "18") (pinfunction "18_18") (pintype "passive"))
    )
    (net (code "76") (name "GND") (class "Default")
      (node (ref "J1") (pin "26") (pinfunction "MH1_26") (pintype "passive"))
      (node (ref "J1") (pin "27") (pinfunction "MH2_27") (pintype "passive"))
      (node (ref "J2") (pin "4") (pinfunction "GND_4") (pintype "power_in"))
      (node (ref "J3") (pin "10") (pinfunction "MH1_10") (pintype "passive"))
      (node (ref "J3") (pin "11") (pinfunction "MH2_11") (pintype "passive"))
      (node (ref "J3") (pin "2") (pinfunction "2_2") (pintype "passive"))
      (node (ref "P14") (pin "1") (pinfunction "1_1") (pintype "passive"))
      (node (ref "P14") (pin "2") (pinfunction "2_2") (pintype "passive"))
      (node (ref "P19") (pin "1") (pinfunction "1_1") (pintype "passive"))
      (node (ref "P19") (pin "2") (pinfunction "2_2") (pintype "passive"))
      (node (ref "P2") (pin "2") (pinfunction "2_2") (pintype "passive"))
      (node (ref "P21") (pin "1") (pinfunction "1_1") (pintype "passive"))
      (node (ref "P21") (pin "2") (pinfunction "2_2") (pintype "passive"))
      (node (ref "P23") (pin "1") (pinfunction "1_1") (pintype "passive"))
      (node (ref "P23") (pin "2") (pinfunction "2_2") (pintype "passive"))
      (node (ref "U1") (pin "29") (pinfunction "GND_29") (pintype "passive"))
      (node (ref "U1") (pin "4") (pinfunction "GND_4") (pintype "passive"))
      (node (ref "X1") (pin "12") (pinfunction "GND_12") (pintype "passive"))
      (node (ref "X10") (pin "4") (pinfunction "GND_4") (pintype "passive"))
      (node (ref "X10") (pin "5") (pinfunction "GND_5") (pintype "passive"))
      (node (ref "X10") (pin "6") (pinfunction "GND_6") (pintype "passive"))
      (node (ref "X2") (pin "12") (pinfunction "GND_12") (pintype "passive"))
      (node (ref "X3") (pin "12") (pinfunction "GND_12") (pintype "passive"))
      (node (ref "X4") (pin "12") (pinfunction "GND_12") (pintype "passive"))
      (node (ref "X5") (pin "12") (pinfunction "GND_12") (pintype "passive"))
      (node (ref "X6") (pin "12") (pinfunction "GND_12") (pintype "passive"))
      (node (ref "X7") (pin "12") (pinfunction "GND_12") (pintype "passive"))
      (node (ref "X8") (pin "11") (pinfunction "R1_4_11") (pintype "passive"))
      (node (ref "X8") (pin "12") (pinfunction "GND_12") (pintype "passive"))
      (node (ref "X8") (pin "6") (pinfunction "R1_7_6") (pintype "passive"))
    )
    (net (code "77") (name "unconnected-(J2-SHLD-Pad5)") (class "Default")
      (node (ref "J2") (pin "5") (pinfunction "SHLD_5") (pintype "passive"))
    )
    (net (code "78") (name "unconnected-(J2-SHLD-Pad6)") (class "Default")
      (node (ref "J2") (pin "6") (pinfunction "SHLD_6") (pintype "passive"))
    )
    (net (code "79") (name "unconnected-(J2-VBUS-Pad1)") (class "Default")
      (node (ref "J2") (pin "1") (pinfunction "VBUS_1") (pintype "power_in"))
    )
    (net (code "80") (name "unconnected-(J3-Pad1)") (class "Default")
      (node (ref "J3") (pin "1") (pinfunction "1_1") (pintype "passive"))
    )
    (net (code "81") (name "unconnected-(J3-Pad3)") (class "Default")
      (node (ref "J3") (pin "3") (pinfunction "3_3") (pintype "passive"))
    )
    (net (code "82") (name "unconnected-(J3-Pad4)") (class "Default")
      (node (ref "J3") (pin "4") (pinfunction "4_4") (pintype "passive"))
    )
    (net (code "83") (name "unconnected-(J3-Pad5)") (class "Default")
      (node (ref "J3") (pin "5") (pinfunction "5_5") (pintype "passive"))
    )
    (net (code "84") (name "unconnected-(J3-Pad9)") (class "Default")
      (node (ref "J3") (pin "9") (pinfunction "9_9") (pintype "passive"))
    )
    (net (code "85") (name "unconnected-(U1-+5V-Pad27)") (class "Default")
      (node (ref "U1") (pin "27") (pinfunction "+5V_27") (pintype "passive"))
    )
    (net (code "86") (name "unconnected-(U1-3V3-Pad17)") (class "Default")
      (node (ref "U1") (pin "17") (pinfunction "3V3_17") (pintype "passive"))
    )
    (net (code "87") (name "unconnected-(U1-A6-Pad25)") (class "Default")
      (node (ref "U1") (pin "25") (pinfunction "A6_25") (pintype "passive"))
    )
    (net (code "88") (name "unconnected-(U1-A7-Pad26)") (class "Default")
      (node (ref "U1") (pin "26") (pinfunction "A7_26") (pintype "passive"))
    )
    (net (code "89") (name "unconnected-(U1-AREF-Pad18)") (class "Default")
      (node (ref "U1") (pin "18") (pinfunction "AREF_18") (pintype "passive"))
    )
    (net (code "90") (name "unconnected-(U1-D6-Pad9)") (class "Default")
      (node (ref "U1") (pin "9") (pinfunction "D6_9") (pintype "passive"))
    )
    (net (code "91") (name "unconnected-(U1-RST-Pad3)") (class "Default")
      (node (ref "U1") (pin "3") (pinfunction "RST_3") (pintype "passive"))
    )
    (net (code "92") (name "unconnected-(U1-RST-Pad28)") (class "Default")
      (node (ref "U1") (pin "28") (pinfunction "RST_28") (pintype "passive"))
    )
    (net (code "93") (name "unconnected-(U1-RX-Pad2)") (class "Default")
      (node (ref "U1") (pin "2") (pinfunction "RX_2") (pintype "passive"))
    )
    (net (code "94") (name "unconnected-(U1-TX-Pad1)") (class "Default")
      (node (ref "U1") (pin "1") (pinfunction "TX_1") (pintype "passive"))
    )
    (net (code "95") (name "unconnected-(U1-VIN-Pad30)") (class "Default")
      (node (ref "U1") (pin "30") (pinfunction "VIN_30") (pintype "passive"))
    )
    (net (code "96") (name "unconnected-(X1-R1_5-Pad4)") (class "Default")
      (node (ref "X1") (pin "4") (pinfunction "R1_5_4") (pintype "passive"))
    )
    (net (code "97") (name "unconnected-(X1-R1_6-Pad5)") (class "Default")
      (node (ref "X1") (pin "5") (pinfunction "R1_6_5") (pintype "passive"))
    )
    (net (code "98") (name "unconnected-(X1-R1_7-Pad6)") (class "Default")
      (node (ref "X1") (pin "6") (pinfunction "R1_7_6") (pintype "passive"))
    )
    (net (code "99") (name "unconnected-(X1-R2_5-Pad1)") (class "Default")
      (node (ref "X1") (pin "1") (pinfunction "R2_5_1") (pintype "passive"))
    )
    (net (code "100") (name "unconnected-(X1-R2_6-Pad2)") (class "Default")
      (node (ref "X1") (pin "2") (pinfunction "R2_6_2") (pintype "passive"))
    )
    (net (code "101") (name "unconnected-(X1-R2_7-Pad3)") (class "Default")
      (node (ref "X1") (pin "3") (pinfunction "R2_7_3") (pintype "passive"))
    )
    (net (code "102") (name "unconnected-(X2-R1_5-Pad4)") (class "Default")
      (node (ref "X2") (pin "4") (pinfunction "R1_5_4") (pintype "passive"))
    )
    (net (code "103") (name "unconnected-(X2-R1_6-Pad5)") (class "Default")
      (node (ref "X2") (pin "5") (pinfunction "R1_6_5") (pintype "passive"))
    )
    (net (code "104") (name "unconnected-(X2-R1_7-Pad6)") (class "Default")
      (node (ref "X2") (pin "6") (pinfunction "R1_7_6") (pintype "passive"))
    )
    (net (code "105") (name "unconnected-(X2-R2_5-Pad1)") (class "Default")
      (node (ref "X2") (pin "1") (pinfunction "R2_5_1") (pintype "passive"))
    )
    (net (code "106") (name "unconnected-(X2-R2_6-Pad2)") (class "Default")
      (node (ref "X2") (pin "2") (pinfunction "R2_6_2") (pintype "passive"))
    )
    (net (code "107") (name "unconnected-(X2-R2_7-Pad3)") (class "Default")
      (node (ref "X2") (pin "3") (pinfunction "R2_7_3") (pintype "passive"))
    )
    (net (code "108") (name "unconnected-(X3-R1_5-Pad4)") (class "Default")
      (node (ref "X3") (pin "4") (pinfunction "R1_5_4") (pintype "passive"))
    )
    (net (code "109") (name "unconnected-(X3-R1_6-Pad5)") (class "Default")
      (node (ref "X3") (pin "5") (pinfunction "R1_6_5") (pintype "passive"))
    )
    (net (code "110") (name "unconnected-(X3-R1_7-Pad6)") (class "Default")
      (node (ref "X3") (pin "6") (pinfunction "R1_7_6") (pintype "passive"))
    )
    (net (code "111") (name "unconnected-(X3-R2_5-Pad1)") (class "Default")
      (node (ref "X3") (pin "1") (pinfunction "R2_5_1") (pintype "passive"))
    )
    (net (code "112") (name "unconnected-(X3-R2_6-Pad2)") (class "Default")
      (node (ref "X3") (pin "2") (pinfunction "R2_6_2") (pintype "passive"))
    )
    (net (code "113") (name "unconnected-(X3-R2_7-Pad3)") (class "Default")
      (node (ref "X3") (pin "3") (pinfunction "R2_7_3") (pintype "passive"))
    )
    (net (code "114") (name "unconnected-(X4-R1_5-Pad4)") (class "Default")
      (node (ref "X4") (pin "4") (pinfunction "R1_5_4") (pintype "passive"))
    )
    (net (code "115") (name "unconnected-(X4-R1_6-Pad5)") (class "Default")
      (node (ref "X4") (pin "5") (pinfunction "R1_6_5") (pintype "passive"))
    )
    (net (code "116") (name "unconnected-(X4-R1_7-Pad6)") (class "Default")
      (node (ref "X4") (pin "6") (pinfunction "R1_7_6") (pintype "passive"))
    )
    (net (code "117") (name "unconnected-(X4-R2_5-Pad1)") (class "Default")
      (node (ref "X4") (pin "1") (pinfunction "R2_5_1") (pintype "passive"))
    )
    (net (code "118") (name "unconnected-(X4-R2_6-Pad2)") (class "Default")
      (node (ref "X4") (pin "2") (pinfunction "R2_6_2") (pintype "passive"))
    )
    (net (code "119") (name "unconnected-(X4-R2_7-Pad3)") (class "Default")
      (node (ref "X4") (pin "3") (pinfunction "R2_7_3") (pintype "passive"))
    )
    (net (code "120") (name "unconnected-(X5-R1_5-Pad4)") (class "Default")
      (node (ref "X5") (pin "4") (pinfunction "R1_5_4") (pintype "passive"))
    )
    (net (code "121") (name "unconnected-(X5-R1_6-Pad5)") (class "Default")
      (node (ref "X5") (pin "5") (pinfunction "R1_6_5") (pintype "passive"))
    )
    (net (code "122") (name "unconnected-(X5-R1_7-Pad6)") (class "Default")
      (node (ref "X5") (pin "6") (pinfunction "R1_7_6") (pintype "passive"))
    )
    (net (code "123") (name "unconnected-(X5-R2_5-Pad1)") (class "Default")
      (node (ref "X5") (pin "1") (pinfunction "R2_5_1") (pintype "passive"))
    )
    (net (code "124") (name "unconnected-(X5-R2_6-Pad2)") (class "Default")
      (node (ref "X5") (pin "2") (pinfunction "R2_6_2") (pintype "passive"))
    )
    (net (code "125") (name "unconnected-(X5-R2_7-Pad3)") (class "Default")
      (node (ref "X5") (pin "3") (pinfunction "R2_7_3") (pintype "passive"))
    )
    (net (code "126") (name "unconnected-(X6-R1_5-Pad4)") (class "Default")
      (node (ref "X6") (pin "4") (pinfunction "R1_5_4") (pintype "passive"))
    )
    (net (code "127") (name "unconnected-(X6-R1_6-Pad5)") (class "Default")
      (node (ref "X6") (pin "5") (pinfunction "R1_6_5") (pintype "passive"))
    )
    (net (code "128") (name "unconnected-(X6-R1_7-Pad6)") (class "Default")
      (node (ref "X6") (pin "6") (pinfunction "R1_7_6") (pintype "passive"))
    )
    (net (code "129") (name "unconnected-(X6-R2_5-Pad1)") (class "Default")
      (node (ref "X6") (pin "1") (pinfunction "R2_5_1") (pintype "passive"))
    )
    (net (code "130") (name "unconnected-(X6-R2_6-Pad2)") (class "Default")
      (node (ref "X6") (pin "2") (pinfunction "R2_6_2") (pintype "passive"))
    )
    (net (code "131") (name "unconnected-(X6-R2_7-Pad3)") (class "Default")
      (node (ref "X6") (pin "3") (pinfunction "R2_7_3") (pintype "passive"))
    )
    (net (code "132") (name "unconnected-(X7-R1_5-Pad4)") (class "Default")
      (node (ref "X7") (pin "4") (pinfunction "R1_5_4") (pintype "passive"))
    )
    (net (code "133") (name "unconnected-(X7-R1_6-Pad5)") (class "Default")
      (node (ref "X7") (pin "5") (pinfunction "R1_6_5") (pintype "passive"))
    )
    (net (code "134") (name "unconnected-(X7-R1_7-Pad6)") (class "Default")
      (node (ref "X7") (pin "6") (pinfunction "R1_7_6") (pintype "passive"))
    )
    (net (code "135") (name "unconnected-(X7-R2_5-Pad1)") (class "Default")
      (node (ref "X7") (pin "1") (pinfunction "R2_5_1") (pintype "passive"))
    )
    (net (code "136") (name "unconnected-(X7-R2_6-Pad2)") (class "Default")
      (node (ref "X7") (pin "2") (pinfunction "R2_6_2") (pintype "passive"))
    )
    (net (code "137") (name "unconnected-(X7-R2_7-Pad3)") (class "Default")
      (node (ref "X7") (pin "3") (pinfunction "R2_7_3") (pintype "passive"))
    )
    (net (code "138") (name "unconnected-(X8-R2_5-Pad1)") (class "Default")
      (node (ref "X8") (pin "1") (pinfunction "R2_5_1") (pintype "passive"))
    )
    (net (code "139") (name "unconnected-(X8-R2_6-Pad2)") (class "Default")
      (node (ref "X8") (pin "2") (pinfunction "R2_6_2") (pintype "passive"))
    )
    (net (code "140") (name "unconnected-(X8-R2_7-Pad3)") (class "Default")
      (node (ref "X8") (pin "3") (pinfunction "R2_7_3") (pintype "passive"))
    )
    (net (code "141") (name "unconnected-(X9-+V-Pad3)") (class "Default")
      (node (ref "X9") (pin "3") (pinfunction "+V_3") (pintype "passive"))
    )
    (net (code "142") (name "unconnected-(X9--V-Pad4)") (class "Default")
      (node (ref "X9") (pin "4") (pinfunction "-V_4") (pintype "passive"))
    )
  )
)
